# B_PCB.net
KiCad netlist of a schematic drawn in EAGLE
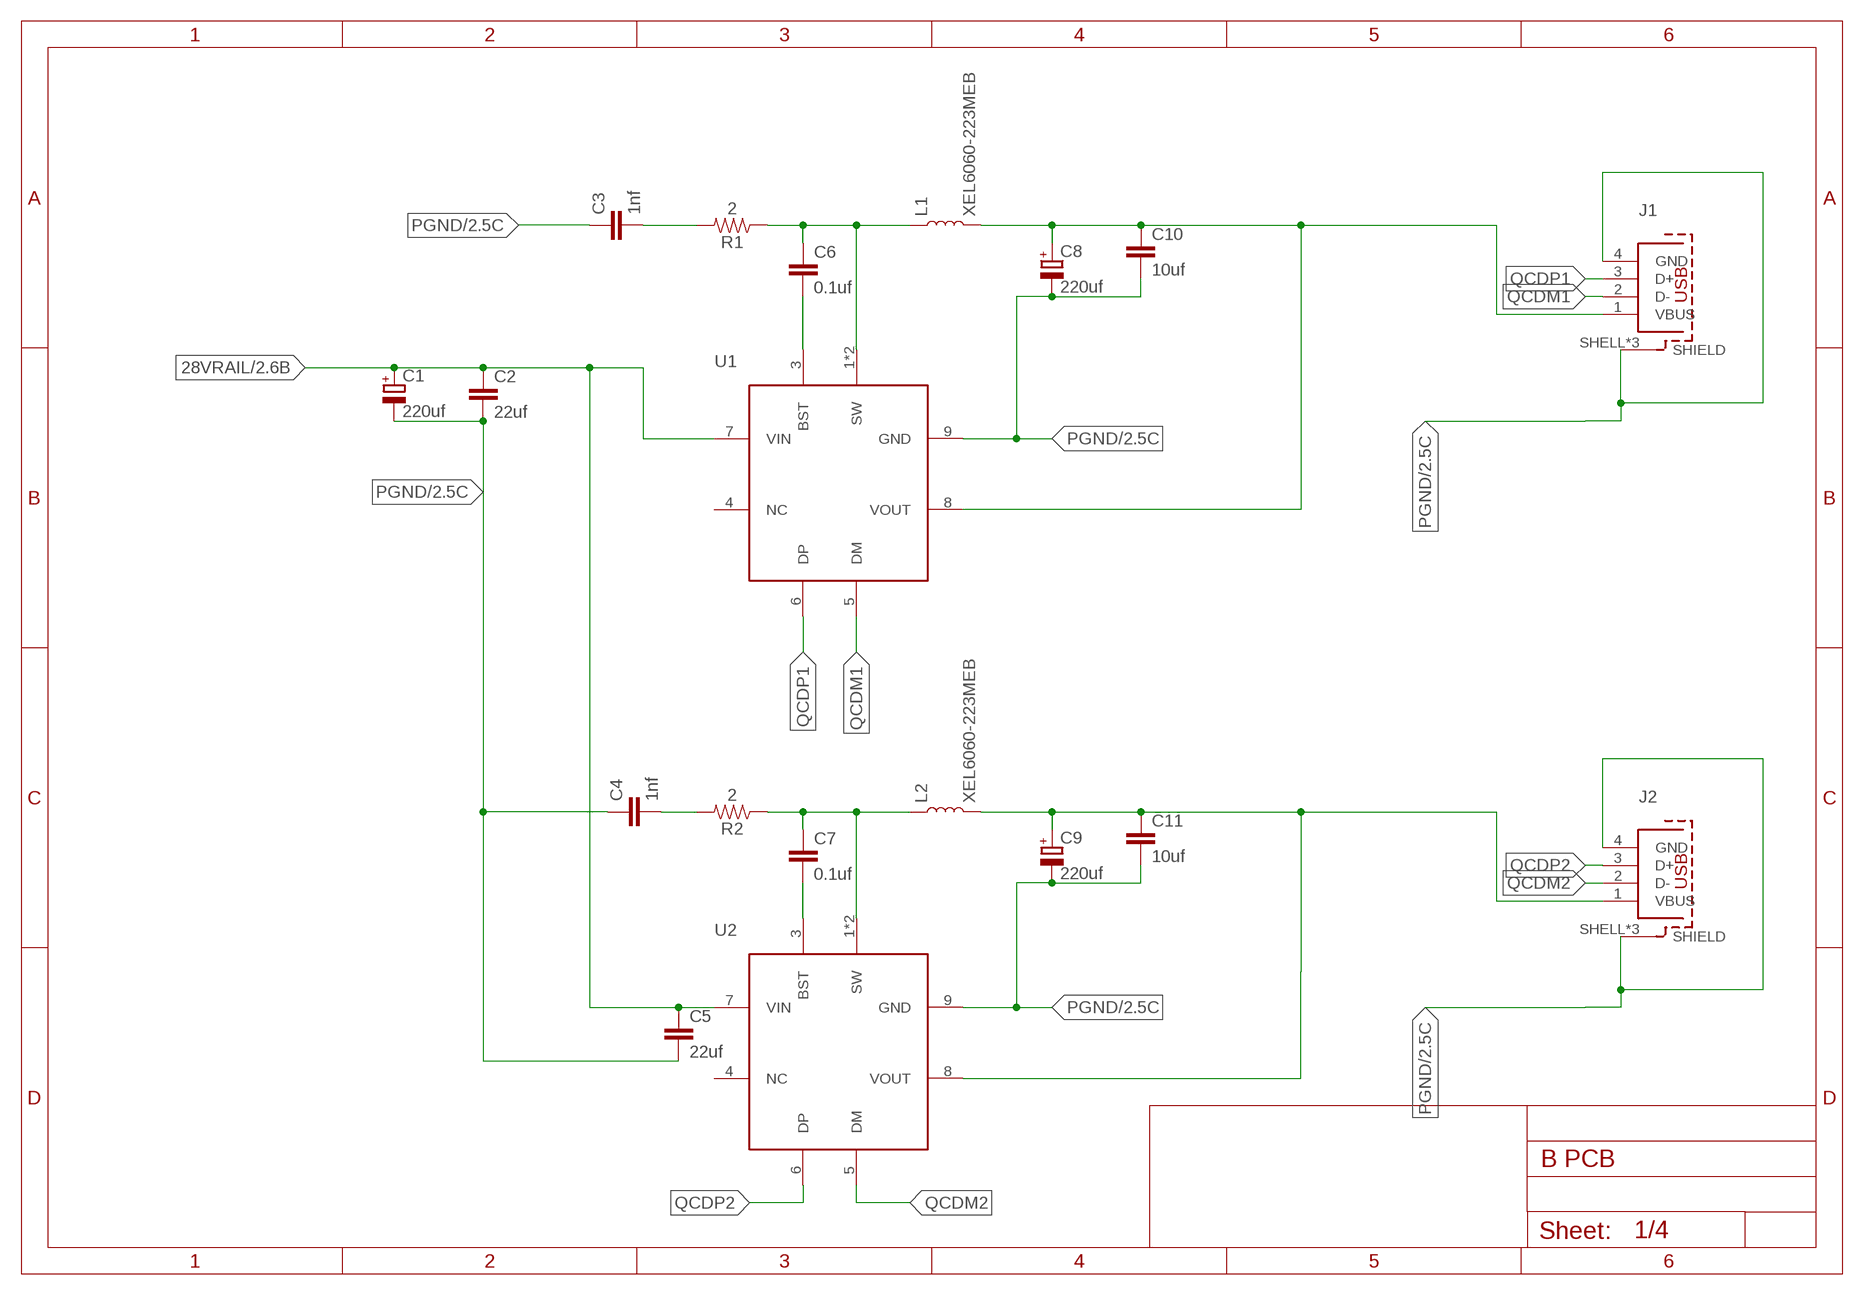
[diagram p0: schematic, sheet 1]
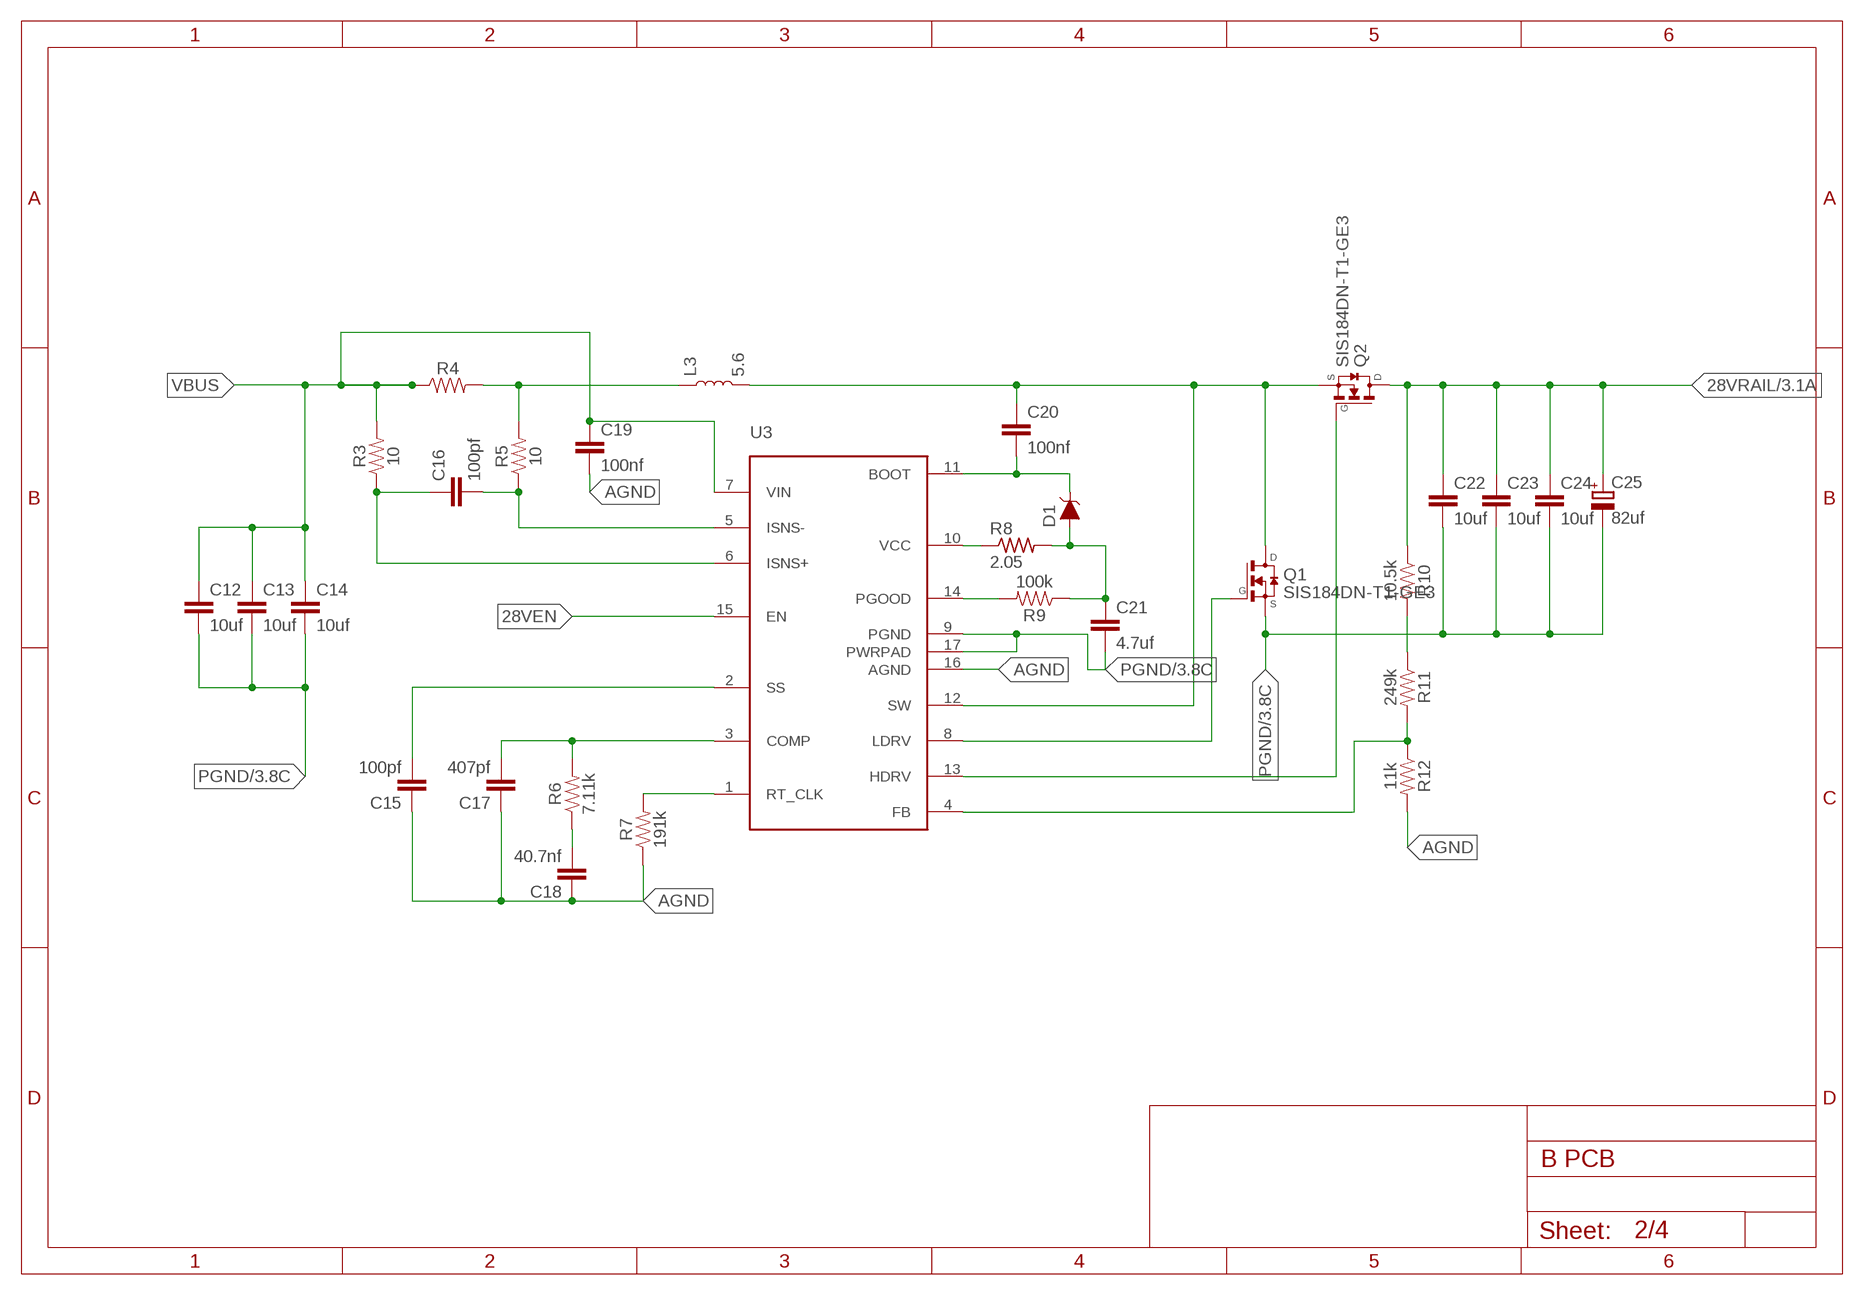
[diagram p1: schematic, sheet 2]
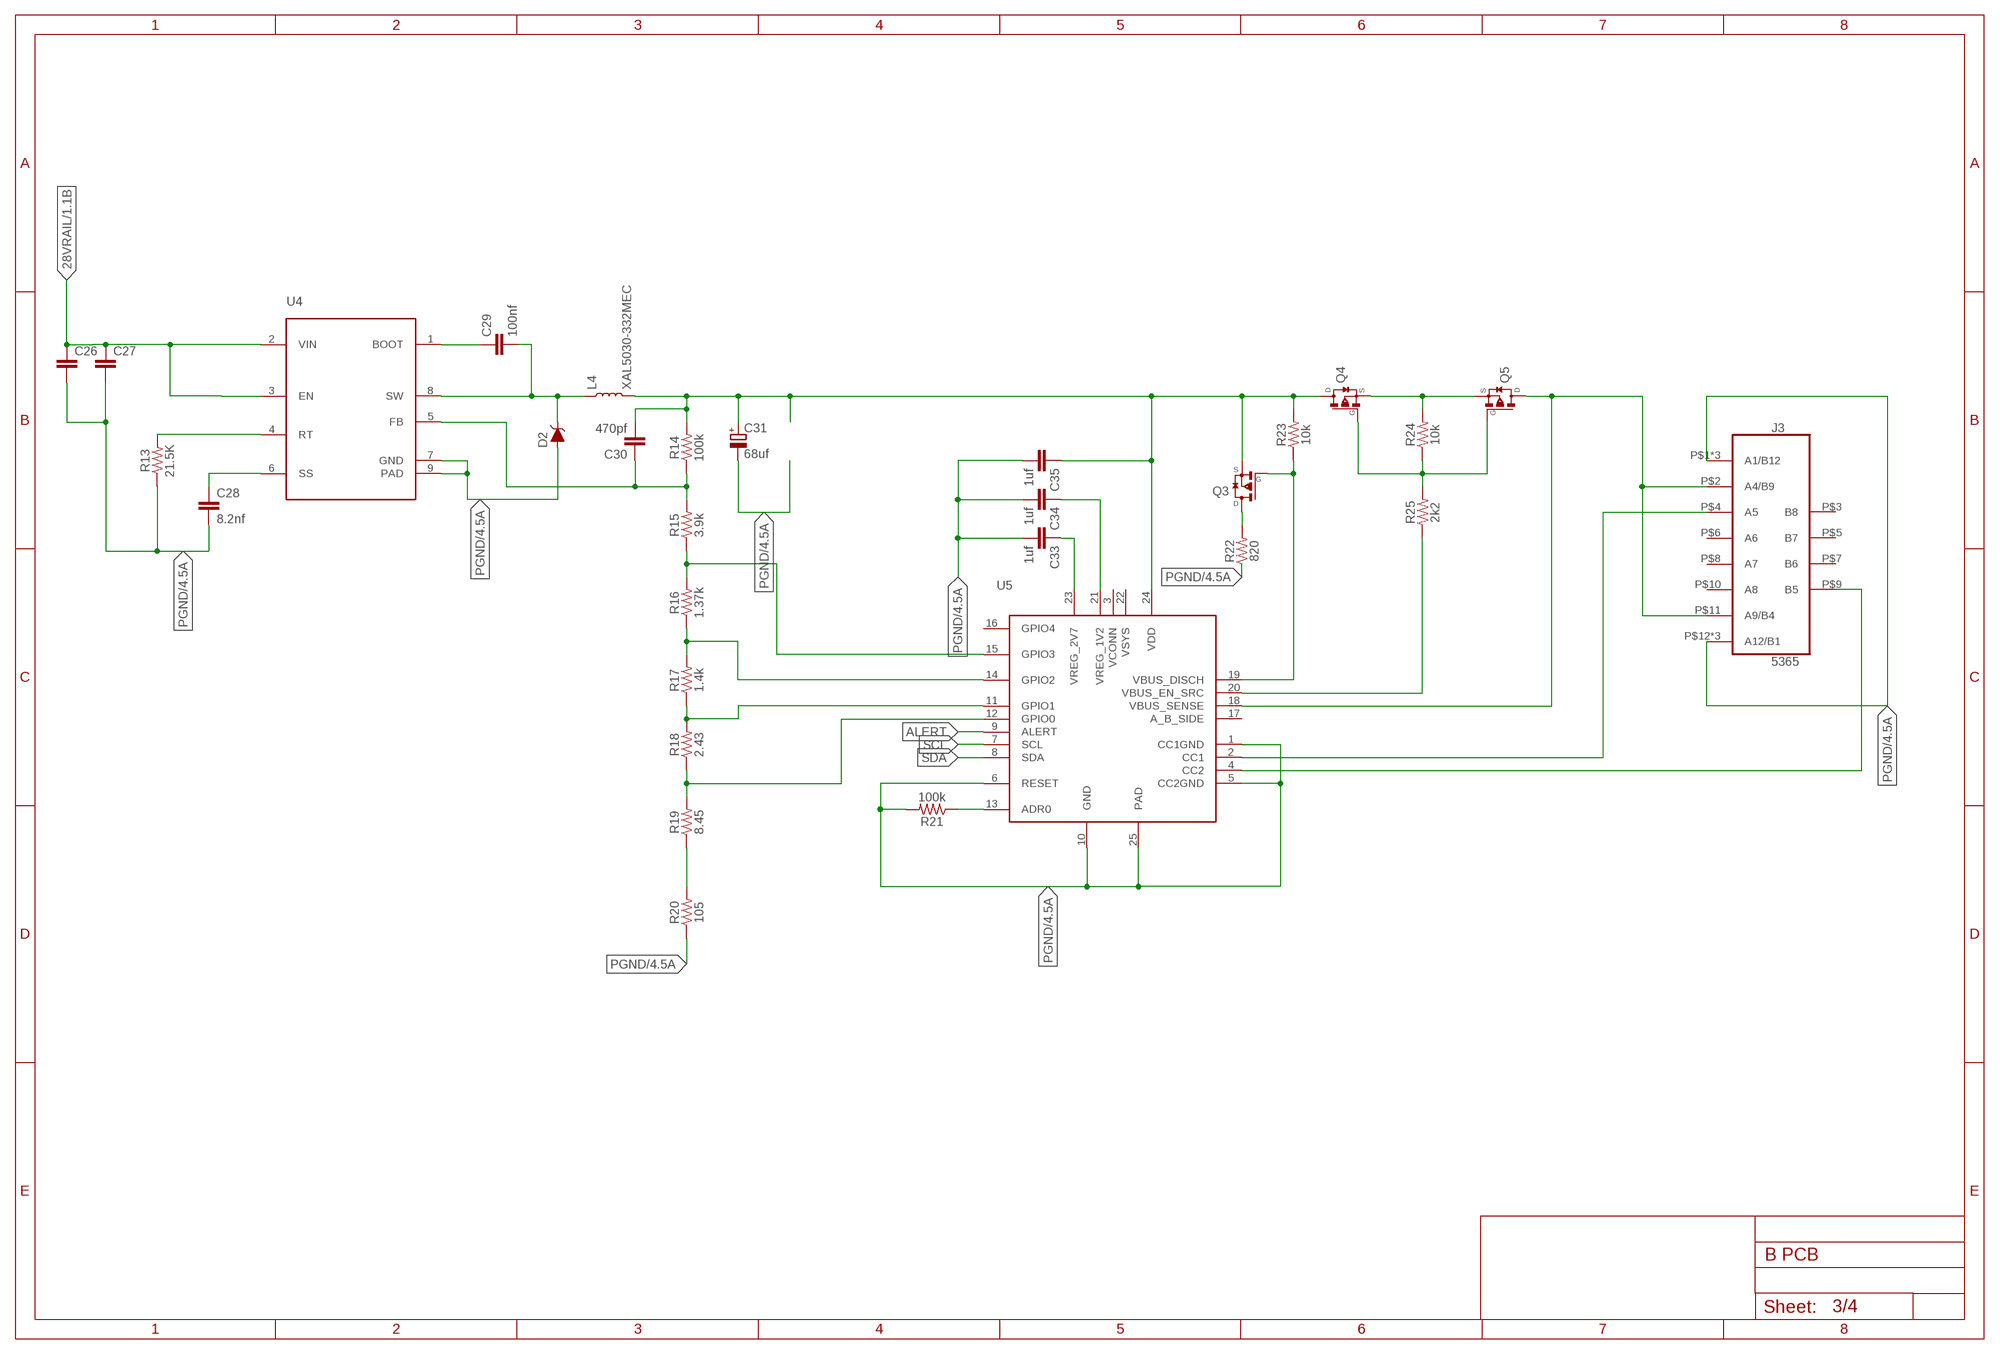
[diagram p2: schematic, sheet 3]
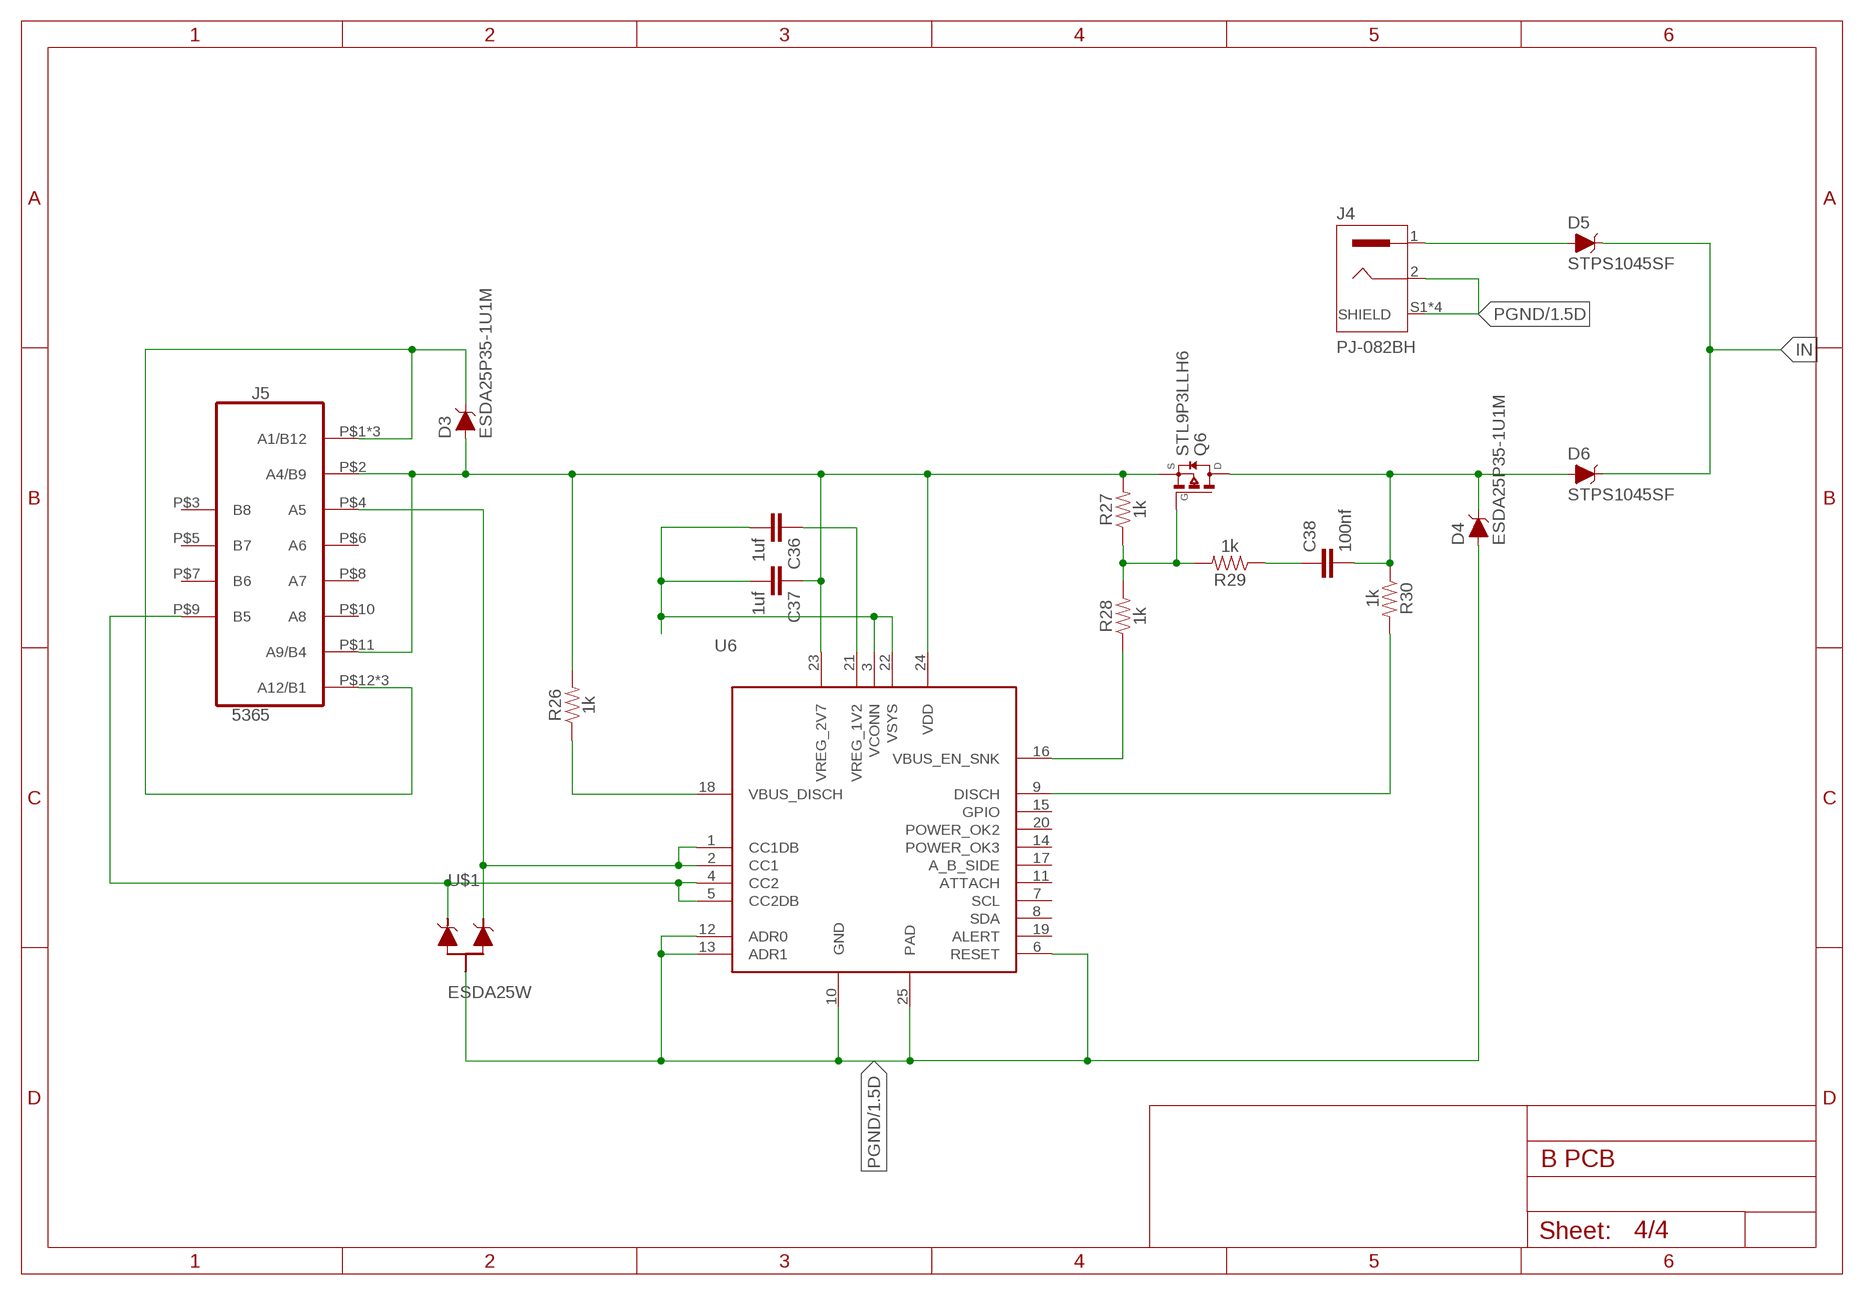
[diagram p3: schematic, sheet 4]

(export (version "E")
  (design (tool "Eeschema 10.0.6"))
  (components
    (comp (ref "C36")
      (value "1uf")
      (footprint "eagle-import:C0402K")
      (libsource (lib "eagle-import") (part "C-EUC0402K"))
    )
    (comp (ref "C37")
      (value "1uf")
      (footprint "eagle-import:C0402K")
      (libsource (lib "eagle-import") (part "C-EUC0402K"))
    )
    (comp (ref "C38")
      (value "100nf")
      (footprint "eagle-import:C0402K")
      (libsource (lib "eagle-import") (part "C-EUC0402K"))
    )
    (comp (ref "D3")
      (value "ESDA25P35-1U1M")
      (footprint "eagle-import:DIODFN160X100X60-2")
      (libsource (lib "eagle-import") (part "ESDA25P35-1U1M"))
    )
    (comp (ref "D4")
      (value "ESDA25P35-1U1M")
      (footprint "eagle-import:DIODFN160X100X60-2")
      (libsource (lib "eagle-import") (part "ESDA25P35-1U1M"))
    )
    (comp (ref "D5")
      (value "STPS1045SF")
      (footprint "eagle-import:DIODFN650X460X120-3")
      (libsource (lib "eagle-import") (part "STPS1045SF"))
    )
    (comp (ref "D6")
      (value "STPS1045SF")
      (footprint "eagle-import:DIODFN650X460X120-3")
      (libsource (lib "eagle-import") (part "STPS1045SF"))
    )
    (comp (ref "J4")
      (value "PJ-082BH")
      (footprint "eagle-import:CUI_PJ-082BH")
      (fields (field (name "MANUFACTURER") "CUI Inc."))
      (libsource (lib "eagle-import") (part "PJ-082BH"))
    )
    (comp (ref "J5")
      (value "5365")
      (footprint "eagle-import:5365")
      (libsource (lib "eagle-import") (part "5365"))
    )
    (comp (ref "Q6")
      (value "STL9P3LLH6")
      (footprint "eagle-import:SON65P330X330X80-8")
      (libsource (lib "eagle-import") (part "STL9P3LLH6"))
    )
    (comp (ref "R26")
      (value "1k")
      (footprint "eagle-import:0402")
      (libsource (lib "eagle-import") (part "RES4K04020402"))
    )
    (comp (ref "R27")
      (value "1k")
      (footprint "eagle-import:0402")
      (libsource (lib "eagle-import") (part "RES4K04020402"))
    )
    (comp (ref "R28")
      (value "1k")
      (footprint "eagle-import:0402")
      (libsource (lib "eagle-import") (part "RES4K04020402"))
    )
    (comp (ref "R29")
      (value "1k")
      (footprint "eagle-import:0402")
      (libsource (lib "eagle-import") (part "RES4K04020402"))
    )
    (comp (ref "R30")
      (value "1k")
      (footprint "eagle-import:0402")
      (libsource (lib "eagle-import") (part "RES4K04020402"))
    )
    (comp (ref "U$1")
      (value "ESDA25W")
      (footprint "eagle-import:SOT65P210X110-3")
      (libsource (lib "eagle-import") (part "ESDA25W"))
    )
    (comp (ref "U6")
      (value "STUSB4500")
      (footprint "eagle-import:QFN50P400X400X100-25T270")
      (libsource (lib "eagle-import") (part "STUSB4500"))
    )
    (comp (ref "C12")
      (value "10uf")
      (footprint "eagle-import:C0805K")
      (libsource (lib "eagle-import") (part "C-EUC0805K"))
    )
    (comp (ref "C13")
      (value "10uf")
      (footprint "eagle-import:C0805K")
      (libsource (lib "eagle-import") (part "C-EUC0805K"))
    )
    (comp (ref "C14")
      (value "10uf")
      (footprint "eagle-import:C0805K")
      (libsource (lib "eagle-import") (part "C-EUC0805K"))
    )
    (comp (ref "C15")
      (value "100pf")
      (footprint "eagle-import:C0402K")
      (libsource (lib "eagle-import") (part "C-EUC0402K"))
    )
    (comp (ref "C16")
      (value "100pf")
      (footprint "eagle-import:C0402K")
      (libsource (lib "eagle-import") (part "C-EUC0402K"))
    )
    (comp (ref "C17")
      (value "407pf")
      (footprint "eagle-import:C0402K")
      (libsource (lib "eagle-import") (part "C-EUC0402K"))
    )
    (comp (ref "C18")
      (value "40.7nf")
      (footprint "eagle-import:C0402K")
      (libsource (lib "eagle-import") (part "C-EUC0402K"))
    )
    (comp (ref "C19")
      (value "100nf")
      (footprint "eagle-import:C0402K")
      (libsource (lib "eagle-import") (part "C-EUC0402K"))
    )
    (comp (ref "C20")
      (value "100nf")
      (footprint "eagle-import:C0402K")
      (libsource (lib "eagle-import") (part "C-EUC0402K"))
    )
    (comp (ref "C21")
      (value "4.7uf")
      (footprint "eagle-import:C0402K")
      (libsource (lib "eagle-import") (part "C-EUC0402K"))
    )
    (comp (ref "C22")
      (value "10uf")
      (footprint "eagle-import:C0805K")
      (libsource (lib "eagle-import") (part "C-EUC0805K"))
    )
    (comp (ref "C23")
      (value "10uf")
      (footprint "eagle-import:C0805K")
      (libsource (lib "eagle-import") (part "C-EUC0805K"))
    )
    (comp (ref "C24")
      (value "10uf")
      (footprint "eagle-import:C0805K")
      (libsource (lib "eagle-import") (part "C-EUC0805K"))
    )
    (comp (ref "C25")
      (value "82uf")
      (footprint "eagle-import:CAPAE660X800")
      (libsource (lib "eagle-import") (part "EMZR250ARA221MF80G"))
    )
    (comp (ref "D1")
      (value "SS24FL")
      (footprint "eagle-import:SODFL3617X108")
      (libsource (lib "eagle-import") (part "SS24FL"))
    )
    (comp (ref "L3")
      (value "5.6")
      (footprint "eagle-import:RESM7275X700")
      (libsource (lib "eagle-import") (part "XAL7070-472MEB"))
    )
    (comp (ref "Q1")
      (value "SIS184DN-T1-GE3")
      (footprint "eagle-import:SIS184DN-T1-GE3")
      (libsource (lib "eagle-import") (part "SIS184DN-T1-GE3"))
    )
    (comp (ref "Q2")
      (value "SIS184DN-T1-GE3")
      (footprint "eagle-import:SIS184DN-T1-GE3")
      (libsource (lib "eagle-import") (part "SIS184DN-T1-GE3"))
    )
    (comp (ref "R3")
      (value "10")
      (footprint "eagle-import:0402")
      (libsource (lib "eagle-import") (part "RES4K04020402"))
    )
    (comp (ref "R4")
      (value "LRMAM2512-R0035FT4")
      (footprint "eagle-import:RESC6432X90")
      (libsource (lib "eagle-import") (part "LRMAM2512-R0035FT4"))
    )
    (comp (ref "R5")
      (value "10")
      (footprint "eagle-import:0402")
      (libsource (lib "eagle-import") (part "RES4K04020402"))
    )
    (comp (ref "R6")
      (value "7.11k")
      (footprint "eagle-import:0402")
      (libsource (lib "eagle-import") (part "RES4K04020402"))
    )
    (comp (ref "R7")
      (value "191k")
      (footprint "eagle-import:0402")
      (libsource (lib "eagle-import") (part "RES4K04020402"))
    )
    (comp (ref "R8")
      (value "2.05")
      (footprint "eagle-import:R0603")
      (libsource (lib "eagle-import") (part "R-US_R0603"))
    )
    (comp (ref "R9")
      (value "100k")
      (footprint "eagle-import:0402")
      (libsource (lib "eagle-import") (part "RES4K04020402"))
    )
    (comp (ref "R10")
      (value "10.5k")
      (footprint "eagle-import:0402")
      (libsource (lib "eagle-import") (part "RES4K04020402"))
    )
    (comp (ref "R11")
      (value "249k")
      (footprint "eagle-import:0402")
      (libsource (lib "eagle-import") (part "RES4K04020402"))
    )
    (comp (ref "R12")
      (value "11k")
      (footprint "eagle-import:0402")
      (libsource (lib "eagle-import") (part "RES4K04020402"))
    )
    (comp (ref "U3")
      (value "TPS43061")
      (footprint "eagle-import:QFN50P300X300X100-17T80X120")
      (libsource (lib "eagle-import") (part "TPS43061"))
    )
    (comp (ref "C1")
      (value "220uf")
      (footprint "eagle-import:CAPAE830X1040")
      (libsource (lib "eagle-import") (part "PCR1H820MCL6GS"))
    )
    (comp (ref "C2")
      (value "22uf")
      (footprint "eagle-import:C0805K")
      (libsource (lib "eagle-import") (part "C-EUC0805K"))
    )
    (comp (ref "C3")
      (value "1nf")
      (footprint "eagle-import:C0402K")
      (libsource (lib "eagle-import") (part "C-EUC0402K"))
    )
    (comp (ref "C4")
      (value "1nf")
      (footprint "eagle-import:C0402K")
      (libsource (lib "eagle-import") (part "C-EUC0402K"))
    )
    (comp (ref "C5")
      (value "22uf")
      (footprint "eagle-import:C0805K")
      (libsource (lib "eagle-import") (part "C-EUC0805K"))
    )
    (comp (ref "C6")
      (value "0.1uf")
      (footprint "eagle-import:C0805K")
      (libsource (lib "eagle-import") (part "C-EUC0805K"))
    )
    (comp (ref "C7")
      (value "0.1uf")
      (footprint "eagle-import:C0805K")
      (libsource (lib "eagle-import") (part "C-EUC0805K"))
    )
    (comp (ref "C8")
      (value "220uf")
      (footprint "eagle-import:CAPAE660X800")
      (libsource (lib "eagle-import") (part "EMZR250ARA221MF80G"))
    )
    (comp (ref "C9")
      (value "220uf")
      (footprint "eagle-import:CAPAE660X800")
      (libsource (lib "eagle-import") (part "EMZR250ARA221MF80G"))
    )
    (comp (ref "C10")
      (value "10uf")
      (footprint "eagle-import:C0805K")
      (libsource (lib "eagle-import") (part "C-EUC0805K"))
    )
    (comp (ref "C11")
      (value "10uf")
      (footprint "eagle-import:C0805K")
      (libsource (lib "eagle-import") (part "C-EUC0805K"))
    )
    (comp (ref "J1")
      (value "614004184726")
      (footprint "eagle-import:614004184726")
      (libsource (lib "eagle-import") (part "614004184726"))
    )
    (comp (ref "J2")
      (value "614004184726")
      (footprint "eagle-import:614004184726")
      (libsource (lib "eagle-import") (part "614004184726"))
    )
    (comp (ref "L1")
      (value "XEL6060-223MEB")
      (footprint "eagle-import:RESM6365X610")
      (libsource (lib "eagle-import") (part "XEL6060-222MEB"))
    )
    (comp (ref "L2")
      (value "XEL6060-223MEB")
      (footprint "eagle-import:RESM6365X610")
      (libsource (lib "eagle-import") (part "XEL6060-222MEB"))
    )
    (comp (ref "R1")
      (value "2")
      (footprint "eagle-import:0402")
      (libsource (lib "eagle-import") (part "RES4K04020402"))
    )
    (comp (ref "R2")
      (value "2")
      (footprint "eagle-import:0402")
      (libsource (lib "eagle-import") (part "RES4K04020402"))
    )
    (comp (ref "U1")
      (value "IP6505")
      (footprint "eagle-import:SOIC127P600X165-9T209")
      (libsource (lib "eagle-import") (part "IP6505"))
    )
    (comp (ref "U2")
      (value "IP6505")
      (footprint "eagle-import:SOIC127P600X165-9T209")
      (libsource (lib "eagle-import") (part "IP6505"))
    )
    (comp (ref "C26")
      (value "C-EUC1210")
      (footprint "eagle-import:C1210")
      (libsource (lib "eagle-import") (part "C-EUC1210"))
    )
    (comp (ref "C27")
      (value "C-EUC1210")
      (footprint "eagle-import:C1210")
      (libsource (lib "eagle-import") (part "C-EUC1210"))
    )
    (comp (ref "C28")
      (value "8.2nf")
      (footprint "eagle-import:C0402K")
      (libsource (lib "eagle-import") (part "C-EUC0402K"))
    )
    (comp (ref "C29")
      (value "100nf")
      (footprint "eagle-import:C0402K")
      (libsource (lib "eagle-import") (part "C-EUC0402K"))
    )
    (comp (ref "C30")
      (value "470pf")
      (footprint "eagle-import:C0402K")
      (libsource (lib "eagle-import") (part "C-EUC0402K"))
    )
    (comp (ref "C31")
      (value "68uf")
      (footprint "eagle-import:CAPAE830X1040")
      (libsource (lib "eagle-import") (part "PCR1H820MCL6GS"))
    )
    (comp (ref "C33")
      (value "1uf")
      (footprint "eagle-import:C0402K")
      (libsource (lib "eagle-import") (part "C-EUC0402K"))
    )
    (comp (ref "C34")
      (value "1uf")
      (footprint "eagle-import:C0402K")
      (libsource (lib "eagle-import") (part "C-EUC0402K"))
    )
    (comp (ref "C35")
      (value "1uf")
      (footprint "eagle-import:C0402K")
      (libsource (lib "eagle-import") (part "C-EUC0402K"))
    )
    (comp (ref "D2")
      (value "B560C-13-F")
      (footprint "eagle-import:DIOM6859X250")
      (libsource (lib "eagle-import") (part "B560C-13-F"))
    )
    (comp (ref "J3")
      (value "5365")
      (footprint "eagle-import:5365")
      (libsource (lib "eagle-import") (part "5365"))
    )
    (comp (ref "L4")
      (value "XAL5030-332MEC")
      (footprint "eagle-import:INDM5355X310")
      (libsource (lib "eagle-import") (part "XAL5030-332MEC"))
    )
    (comp (ref "Q3")
      (value "STR2P3LLH6")
      (footprint "eagle-import:SOT95P280X125-3")
      (libsource (lib "eagle-import") (part "STR2P3LLH6"))
    )
    (comp (ref "Q4")
      (value "STL9P3LLH6")
      (footprint "eagle-import:SON65P330X330X80-8")
      (libsource (lib "eagle-import") (part "STL9P3LLH6"))
    )
    (comp (ref "Q5")
      (value "STL9P3LLH6")
      (footprint "eagle-import:SON65P330X330X80-8")
      (libsource (lib "eagle-import") (part "STL9P3LLH6"))
    )
    (comp (ref "R13")
      (value "21.5K")
      (footprint "eagle-import:0402")
      (libsource (lib "eagle-import") (part "RES4K04020402"))
    )
    (comp (ref "R14")
      (value "100k")
      (footprint "eagle-import:0402")
      (libsource (lib "eagle-import") (part "RES4K04020402"))
    )
    (comp (ref "R15")
      (value "3.9k")
      (footprint "eagle-import:0402")
      (libsource (lib "eagle-import") (part "RES4K04020402"))
    )
    (comp (ref "R16")
      (value "1.37k")
      (footprint "eagle-import:0402")
      (libsource (lib "eagle-import") (part "RES4K04020402"))
    )
    (comp (ref "R17")
      (value "1.4k")
      (footprint "eagle-import:0402")
      (libsource (lib "eagle-import") (part "RES4K04020402"))
    )
    (comp (ref "R18")
      (value "2.43")
      (footprint "eagle-import:0402")
      (libsource (lib "eagle-import") (part "RES4K04020402"))
    )
    (comp (ref "R19")
      (value "8.45")
      (footprint "eagle-import:0402")
      (libsource (lib "eagle-import") (part "RES4K04020402"))
    )
    (comp (ref "R20")
      (value "105")
      (footprint "eagle-import:0402")
      (libsource (lib "eagle-import") (part "RES4K04020402"))
    )
    (comp (ref "R21")
      (value "100k")
      (footprint "eagle-import:0402")
      (fields (field (name "SPICEPREFIX") "R"))
      (libsource (lib "eagle-import") (part "RES4K04020402"))
    )
    (comp (ref "R22")
      (value "820")
      (footprint "eagle-import:0402")
      (libsource (lib "eagle-import") (part "RES4K04020402"))
    )
    (comp (ref "R23")
      (value "10k")
      (footprint "eagle-import:0402")
      (libsource (lib "eagle-import") (part "RES4K04020402"))
    )
    (comp (ref "R24")
      (value "10k")
      (footprint "eagle-import:0402")
      (libsource (lib "eagle-import") (part "RES4K04020402"))
    )
    (comp (ref "R25")
      (value "2k2")
      (footprint "eagle-import:0402")
      (libsource (lib "eagle-import") (part "RES4K04020402"))
    )
    (comp (ref "U4")
      (value "LMR14050")
      (footprint "eagle-import:SOIC127P600X170-9T240X260")
      (libsource (lib "eagle-import") (part "LMR14050"))
    )
    (comp (ref "U5")
      (value "STUSB4700")
      (footprint "eagle-import:QFN50P400X400X100-25T270")
      (libsource (lib "eagle-import") (part "STUSB4700"))
    )
  )
  (nets
    (net (code "1") (name "28VEN") (class "Default")
      (node (ref "U3") (pin "15") (pinfunction "EN_15") (pintype "bidirectional"))
    )
    (net (code "2") (name "28VRAIL") (class "Default")
      (node (ref "C1") (pin "1") (pinfunction "+_1") (pintype "passive"))
      (node (ref "C2") (pin "1") (pinfunction "1_1") (pintype "passive"))
      (node (ref "C22") (pin "1") (pinfunction "1_1") (pintype "passive"))
      (node (ref "C23") (pin "1") (pinfunction "1_1") (pintype "passive"))
      (node (ref "C24") (pin "1") (pinfunction "1_1") (pintype "passive"))
      (node (ref "C25") (pin "1") (pinfunction "+_1") (pintype "passive"))
      (node (ref "C26") (pin "1") (pinfunction "1_1") (pintype "passive"))
      (node (ref "C27") (pin "1") (pinfunction "1_1") (pintype "passive"))
      (node (ref "C5") (pin "1") (pinfunction "1_1") (pintype "passive"))
      (node (ref "Q2") (pin "P$5") (pinfunction "D_P$5") (pintype "passive"))
      (node (ref "Q2") (pin "P$6") (pinfunction "D_P$6") (pintype "passive"))
      (node (ref "Q2") (pin "P$7") (pinfunction "D_P$7") (pintype "passive"))
      (node (ref "Q2") (pin "P$8") (pinfunction "D_P$8") (pintype "passive"))
      (node (ref "Q2") (pin "P$9") (pinfunction "D_P$9") (pintype "passive"))
      (node (ref "R10") (pin "1") (pinfunction "1_1") (pintype "passive"))
      (node (ref "U1") (pin "7") (pinfunction "VIN_7") (pintype "bidirectional"))
      (node (ref "U2") (pin "7") (pinfunction "VIN_7") (pintype "bidirectional"))
      (node (ref "U4") (pin "2") (pinfunction "VIN_2") (pintype "bidirectional"))
      (node (ref "U4") (pin "3") (pinfunction "EN_3") (pintype "bidirectional"))
    )
    (net (code "3") (name "AGND") (class "Default")
      (node (ref "C15") (pin "1") (pinfunction "1_1") (pintype "passive"))
      (node (ref "C17") (pin "1") (pinfunction "1_1") (pintype "passive"))
      (node (ref "C18") (pin "1") (pinfunction "1_1") (pintype "passive"))
      (node (ref "C19") (pin "2") (pinfunction "2_2") (pintype "passive"))
      (node (ref "R12") (pin "2") (pinfunction "2_2") (pintype "passive"))
      (node (ref "R7") (pin "1") (pinfunction "1_1") (pintype "passive"))
      (node (ref "U3") (pin "16") (pinfunction "AGND_16") (pintype "bidirectional"))
    )
    (net (code "4") (name "ALERT") (class "Default")
      (node (ref "U5") (pin "9") (pinfunction "ALERT_9") (pintype "bidirectional"))
    )
    (net (code "5") (name "IN") (class "Default")
      (node (ref "D5") (pin "3") (pinfunction "C_3") (pintype "passive"))
      (node (ref "D6") (pin "3") (pinfunction "C_3") (pintype "passive"))
    )
    (net (code "6") (name "Net-(C3-Pad2)") (class "Default")
      (node (ref "C3") (pin "2") (pinfunction "2_2") (pintype "passive"))
      (node (ref "R1") (pin "2") (pinfunction "2_2") (pintype "passive"))
    )
    (net (code "7") (name "Net-(C4-Pad2)") (class "Default")
      (node (ref "C4") (pin "2") (pinfunction "2_2") (pintype "passive"))
      (node (ref "R2") (pin "2") (pinfunction "2_2") (pintype "passive"))
    )
    (net (code "8") (name "Net-(C6-Pad1)") (class "Default")
      (node (ref "C6") (pin "1") (pinfunction "1_1") (pintype "passive"))
      (node (ref "L1") (pin "1") (pinfunction "1_1") (pintype "passive"))
      (node (ref "R1") (pin "1") (pinfunction "1_1") (pintype "passive"))
      (node (ref "U1") (pin "1") (pinfunction "SW_1") (pintype "bidirectional"))
      (node (ref "U1") (pin "2") (pinfunction "SW_2") (pintype "bidirectional"))
    )
    (net (code "9") (name "Net-(C7-Pad1)") (class "Default")
      (node (ref "C7") (pin "1") (pinfunction "1_1") (pintype "passive"))
      (node (ref "L2") (pin "1") (pinfunction "1_1") (pintype "passive"))
      (node (ref "R2") (pin "1") (pinfunction "1_1") (pintype "passive"))
      (node (ref "U2") (pin "1") (pinfunction "SW_1") (pintype "bidirectional"))
      (node (ref "U2") (pin "2") (pinfunction "SW_2") (pintype "bidirectional"))
    )
    (net (code "10") (name "Net-(C8-+)") (class "Default")
      (node (ref "C10") (pin "1") (pinfunction "1_1") (pintype "passive"))
      (node (ref "C8") (pin "1") (pinfunction "+_1") (pintype "passive"))
      (node (ref "J1") (pin "1") (pinfunction "VBUS_1") (pintype "bidirectional"))
      (node (ref "L1") (pin "2") (pinfunction "2_2") (pintype "passive"))
      (node (ref "U1") (pin "8") (pinfunction "VOUT_8") (pintype "bidirectional"))
    )
    (net (code "11") (name "Net-(C9-+)") (class "Default")
      (node (ref "C11") (pin "1") (pinfunction "1_1") (pintype "passive"))
      (node (ref "C9") (pin "1") (pinfunction "+_1") (pintype "passive"))
      (node (ref "J2") (pin "1") (pinfunction "VBUS_1") (pintype "bidirectional"))
      (node (ref "L2") (pin "2") (pinfunction "2_2") (pintype "passive"))
      (node (ref "U2") (pin "8") (pinfunction "VOUT_8") (pintype "bidirectional"))
    )
    (net (code "12") (name "Net-(C18-Pad2)") (class "Default")
      (node (ref "C18") (pin "2") (pinfunction "2_2") (pintype "passive"))
      (node (ref "R6") (pin "1") (pinfunction "1_1") (pintype "passive"))
    )
    (net (code "13") (name "Net-(C31-+)") (class "Default")
      (node (ref "C30") (pin "2") (pinfunction "2_2") (pintype "passive"))
      (node (ref "C31") (pin "1") (pinfunction "+_1") (pintype "passive"))
      (node (ref "C35") (pin "1") (pinfunction "1_1") (pintype "passive"))
      (node (ref "L4") (pin "2") (pinfunction "2_2") (pintype "passive"))
      (node (ref "Q3") (pin "2") (pinfunction "S_2") (pintype "passive"))
      (node (ref "Q4") (pin "5") (pinfunction "D_5") (pintype "passive"))
      (node (ref "Q4") (pin "6") (pinfunction "D_6") (pintype "passive"))
      (node (ref "Q4") (pin "7") (pinfunction "D_7") (pintype "passive"))
      (node (ref "R14") (pin "2") (pinfunction "2_2") (pintype "passive"))
      (node (ref "R23") (pin "2") (pinfunction "2_2") (pintype "passive"))
      (node (ref "U5") (pin "24") (pinfunction "VDD_24") (pintype "bidirectional"))
    )
    (net (code "14") (name "Net-(C38-Pad1)") (class "Default")
      (node (ref "C38") (pin "1") (pinfunction "1_1") (pintype "passive"))
      (node (ref "R29") (pin "1") (pinfunction "1_1") (pintype "passive"))
    )
    (net (code "15") (name "Net-(D1-A)") (class "Default")
      (node (ref "C21") (pin "1") (pinfunction "1_1") (pintype "passive"))
      (node (ref "D1") (pin "2") (pinfunction "A_2") (pintype "passive"))
      (node (ref "R8") (pin "2") (pinfunction "2_2") (pintype "passive"))
      (node (ref "R9") (pin "1") (pinfunction "1_1") (pintype "passive"))
    )
    (net (code "16") (name "Net-(D1-C)") (class "Default")
      (node (ref "C20") (pin "2") (pinfunction "2_2") (pintype "passive"))
      (node (ref "D1") (pin "1") (pinfunction "C_1") (pintype "passive"))
      (node (ref "U3") (pin "11") (pinfunction "BOOT_11") (pintype "bidirectional"))
    )
    (net (code "17") (name "Net-(D2-C)") (class "Default")
      (node (ref "C29") (pin "2") (pinfunction "2_2") (pintype "passive"))
      (node (ref "D2") (pin "1") (pinfunction "C_1") (pintype "passive"))
      (node (ref "L4") (pin "1") (pinfunction "1_1") (pintype "passive"))
      (node (ref "U4") (pin "8") (pinfunction "SW_8") (pintype "bidirectional"))
    )
    (net (code "18") (name "Net-(D3-A)") (class "Default")
      (node (ref "C37") (pin "1") (pinfunction "1_1") (pintype "passive"))
      (node (ref "D3") (pin "2") (pinfunction "A_2") (pintype "passive"))
      (node (ref "J5") (pin "P$11") (pinfunction "A9/B4_P$11") (pintype "bidirectional"))
      (node (ref "J5") (pin "P$2") (pinfunction "A4/B9_P$2") (pintype "bidirectional"))
      (node (ref "Q6") (pin "1") (pinfunction "S_1") (pintype "passive"))
      (node (ref "Q6") (pin "2") (pinfunction "S_2") (pintype "passive"))
      (node (ref "Q6") (pin "3") (pinfunction "S_3") (pintype "passive"))
      (node (ref "R26") (pin "2") (pinfunction "2_2") (pintype "passive"))
      (node (ref "R27") (pin "2") (pinfunction "2_2") (pintype "passive"))
      (node (ref "U6") (pin "23") (pinfunction "VREG_2V7_23") (pintype "bidirectional"))
      (node (ref "U6") (pin "24") (pinfunction "VDD_24") (pintype "bidirectional"))
    )
    (net (code "19") (name "Net-(D3-C)") (class "Default")
      (node (ref "D3") (pin "1") (pinfunction "C_1") (pintype "passive"))
      (node (ref "J5") (pin "P$1") (pinfunction "A1/B12_P$1") (pintype "bidirectional"))
      (node (ref "J5") (pin "P$12") (pinfunction "A12/B1_P$12") (pintype "bidirectional"))
      (node (ref "J5") (pin "P$13") (pinfunction "A1/B12_P$13") (pintype "bidirectional"))
      (node (ref "J5") (pin "P$14") (pinfunction "A12/B1_P$14") (pintype "bidirectional"))
      (node (ref "J5") (pin "P$15") (pinfunction "A1/B12_P$15") (pintype "bidirectional"))
      (node (ref "J5") (pin "P$16") (pinfunction "A12/B1_P$16") (pintype "bidirectional"))
    )
    (net (code "20") (name "Net-(D4-C)") (class "Default")
      (node (ref "C38") (pin "2") (pinfunction "2_2") (pintype "passive"))
      (node (ref "D4") (pin "1") (pinfunction "C_1") (pintype "passive"))
      (node (ref "D6") (pin "1") (pinfunction "A_1") (pintype "passive"))
      (node (ref "D6") (pin "2") (pinfunction "A_2") (pintype "passive"))
      (node (ref "Q6") (pin "5") (pinfunction "D_5") (pintype "passive"))
      (node (ref "Q6") (pin "6") (pinfunction "D_6") (pintype "passive"))
      (node (ref "Q6") (pin "7") (pinfunction "D_7") (pintype "passive"))
      (node (ref "R30") (pin "1") (pinfunction "1_1") (pintype "passive"))
    )
    (net (code "21") (name "Net-(D5-A-Pad1)") (class "Default")
      (node (ref "D5") (pin "1") (pinfunction "A_1") (pintype "passive"))
      (node (ref "D5") (pin "2") (pinfunction "A_2") (pintype "passive"))
      (node (ref "J4") (pin "1") (pinfunction "1_1") (pintype "passive"))
    )
    (net (code "22") (name "Net-(J3-A4{slash}B9)") (class "Default")
      (node (ref "J3") (pin "P$11") (pinfunction "A9/B4_P$11") (pintype "bidirectional"))
      (node (ref "J3") (pin "P$2") (pinfunction "A4/B9_P$2") (pintype "bidirectional"))
      (node (ref "Q5") (pin "5") (pinfunction "D_5") (pintype "passive"))
      (node (ref "Q5") (pin "6") (pinfunction "D_6") (pintype "passive"))
      (node (ref "Q5") (pin "7") (pinfunction "D_7") (pintype "passive"))
      (node (ref "U5") (pin "18") (pinfunction "VBUS_SENSE_18") (pintype "bidirectional"))
    )
    (net (code "23") (name "Net-(J3-A5)") (class "Default")
      (node (ref "J3") (pin "P$4") (pinfunction "A5_P$4") (pintype "bidirectional"))
      (node (ref "U5") (pin "2") (pinfunction "CC1_2") (pintype "bidirectional"))
    )
    (net (code "24") (name "Net-(J3-B5)") (class "Default")
      (node (ref "J3") (pin "P$9") (pinfunction "B5_P$9") (pintype "bidirectional"))
      (node (ref "U5") (pin "4") (pinfunction "CC2_4") (pintype "bidirectional"))
    )
    (net (code "25") (name "Net-(J5-A5)") (class "Default")
      (node (ref "J5") (pin "P$4") (pinfunction "A5_P$4") (pintype "bidirectional"))
      (node (ref "U$1") (pin "2") (pinfunction "C2_2") (pintype "passive"))
      (node (ref "U6") (pin "1") (pinfunction "CC1DB_1") (pintype "bidirectional"))
      (node (ref "U6") (pin "2") (pinfunction "CC1_2") (pintype "bidirectional"))
    )
    (net (code "26") (name "Net-(J5-B5)") (class "Default")
      (node (ref "J5") (pin "P$9") (pinfunction "B5_P$9") (pintype "bidirectional"))
      (node (ref "U$1") (pin "1") (pinfunction "C1_1") (pintype "passive"))
      (node (ref "U6") (pin "4") (pinfunction "CC2_4") (pintype "bidirectional"))
      (node (ref "U6") (pin "5") (pinfunction "CC2DB_5") (pintype "bidirectional"))
    )
    (net (code "27") (name "Net-(L3-Pad1)") (class "Default")
      (node (ref "L3") (pin "1") (pinfunction "1_1") (pintype "passive"))
      (node (ref "R4") (pin "2") (pinfunction "2_2") (pintype "passive"))
      (node (ref "R5") (pin "2") (pinfunction "2_2") (pintype "passive"))
    )
    (net (code "28") (name "Net-(Q1-G)") (class "Default")
      (node (ref "Q1") (pin "P$4") (pinfunction "G_P$4") (pintype "passive"))
      (node (ref "U3") (pin "8") (pinfunction "LDRV_8") (pintype "bidirectional"))
    )
    (net (code "29") (name "Net-(Q2-G)") (class "Default")
      (node (ref "Q2") (pin "P$4") (pinfunction "G_P$4") (pintype "passive"))
      (node (ref "U3") (pin "13") (pinfunction "HDRV_13") (pintype "bidirectional"))
    )
    (net (code "30") (name "Net-(Q3-D)") (class "Default")
      (node (ref "Q3") (pin "3") (pinfunction "D_3") (pintype "passive"))
      (node (ref "R22") (pin "2") (pinfunction "2_2") (pintype "passive"))
    )
    (net (code "31") (name "Net-(Q3-G)") (class "Default")
      (node (ref "Q3") (pin "1") (pinfunction "G_1") (pintype "passive"))
      (node (ref "R23") (pin "1") (pinfunction "1_1") (pintype "passive"))
      (node (ref "U5") (pin "19") (pinfunction "VBUS_DISCH_19") (pintype "bidirectional"))
    )
    (net (code "32") (name "Net-(Q4-G)") (class "Default")
      (node (ref "Q4") (pin "4") (pinfunction "G_4") (pintype "passive"))
      (node (ref "Q5") (pin "4") (pinfunction "G_4") (pintype "passive"))
      (node (ref "R24") (pin "1") (pinfunction "1_1") (pintype "passive"))
      (node (ref "R25") (pin "2") (pinfunction "2_2") (pintype "passive"))
    )
    (net (code "33") (name "Net-(Q4-S-Pad1)") (class "Default")
      (node (ref "Q4") (pin "1") (pinfunction "S_1") (pintype "passive"))
      (node (ref "Q4") (pin "2") (pinfunction "S_2") (pintype "passive"))
      (node (ref "Q4") (pin "3") (pinfunction "S_3") (pintype "passive"))
      (node (ref "Q5") (pin "1") (pinfunction "S_1") (pintype "passive"))
      (node (ref "Q5") (pin "2") (pinfunction "S_2") (pintype "passive"))
      (node (ref "Q5") (pin "3") (pinfunction "S_3") (pintype "passive"))
      (node (ref "R24") (pin "2") (pinfunction "2_2") (pintype "passive"))
    )
    (net (code "34") (name "Net-(Q6-G)") (class "Default")
      (node (ref "Q6") (pin "4") (pinfunction "G_4") (pintype "passive"))
      (node (ref "R27") (pin "1") (pinfunction "1_1") (pintype "passive"))
      (node (ref "R28") (pin "2") (pinfunction "2_2") (pintype "passive"))
      (node (ref "R29") (pin "2") (pinfunction "2_2") (pintype "passive"))
    )
    (net (code "35") (name "Net-(R10-Pad2)") (class "Default")
      (node (ref "R10") (pin "2") (pinfunction "2_2") (pintype "passive"))
      (node (ref "R11") (pin "1") (pinfunction "1_1") (pintype "passive"))
    )
    (net (code "36") (name "Net-(R19-Pad1)") (class "Default")
      (node (ref "R19") (pin "1") (pinfunction "1_1") (pintype "passive"))
      (node (ref "R20") (pin "2") (pinfunction "2_2") (pintype "passive"))
    )
    (net (code "37") (name "Net-(U1-BST)") (class "Default")
      (node (ref "C6") (pin "2") (pinfunction "2_2") (pintype "passive"))
      (node (ref "U1") (pin "3") (pinfunction "BST_3") (pintype "bidirectional"))
    )
    (net (code "38") (name "Net-(U2-BST)") (class "Default")
      (node (ref "C7") (pin "2") (pinfunction "2_2") (pintype "passive"))
      (node (ref "U2") (pin "3") (pinfunction "BST_3") (pintype "bidirectional"))
    )
    (net (code "39") (name "Net-(U3-COMP)") (class "Default")
      (node (ref "C17") (pin "2") (pinfunction "2_2") (pintype "passive"))
      (node (ref "R6") (pin "2") (pinfunction "2_2") (pintype "passive"))
      (node (ref "U3") (pin "3") (pinfunction "COMP_3") (pintype "bidirectional"))
    )
    (net (code "40") (name "Net-(U3-FB)") (class "Default")
      (node (ref "R11") (pin "2") (pinfunction "2_2") (pintype "passive"))
      (node (ref "R12") (pin "1") (pinfunction "1_1") (pintype "passive"))
      (node (ref "U3") (pin "4") (pinfunction "FB_4") (pintype "bidirectional"))
    )
    (net (code "41") (name "Net-(U3-ISNS+)") (class "Default")
      (node (ref "C16") (pin "1") (pinfunction "1_1") (pintype "passive"))
      (node (ref "R3") (pin "1") (pinfunction "1_1") (pintype "passive"))
      (node (ref "U3") (pin "6") (pinfunction "ISNS+_6") (pintype "bidirectional"))
    )
    (net (code "42") (name "Net-(U3-ISNS-)") (class "Default")
      (node (ref "C16") (pin "2") (pinfunction "2_2") (pintype "passive"))
      (node (ref "R5") (pin "1") (pinfunction "1_1") (pintype "passive"))
      (node (ref "U3") (pin "5") (pinfunction "ISNS-_5") (pintype "bidirectional"))
    )
    (net (code "43") (name "Net-(U3-PGOOD)") (class "Default")
      (node (ref "R9") (pin "2") (pinfunction "2_2") (pintype "passive"))
      (node (ref "U3") (pin "14") (pinfunction "PGOOD_14") (pintype "bidirectional"))
    )
    (net (code "44") (name "Net-(U3-RT_CLK)") (class "Default")
      (node (ref "R7") (pin "2") (pinfunction "2_2") (pintype "passive"))
      (node (ref "U3") (pin "1") (pinfunction "RT_CLK_1") (pintype "bidirectional"))
    )
    (net (code "45") (name "Net-(U3-SS)") (class "Default")
      (node (ref "C15") (pin "2") (pinfunction "2_2") (pintype "passive"))
      (node (ref "U3") (pin "2") (pinfunction "SS_2") (pintype "bidirectional"))
    )
    (net (code "46") (name "Net-(U3-SW)") (class "Default")
      (node (ref "C20") (pin "1") (pinfunction "1_1") (pintype "passive"))
      (node (ref "L3") (pin "2") (pinfunction "2_2") (pintype "passive"))
      (node (ref "Q1") (pin "P$5") (pinfunction "D_P$5") (pintype "passive"))
      (node (ref "Q1") (pin "P$6") (pinfunction "D_P$6") (pintype "passive"))
      (node (ref "Q1") (pin "P$7") (pinfunction "D_P$7") (pintype "passive"))
      (node (ref "Q1") (pin "P$8") (pinfunction "D_P$8") (pintype "passive"))
      (node (ref "Q1") (pin "P$9") (pinfunction "D_P$9") (pintype "passive"))
      (node (ref "Q2") (pin "P$1") (pinfunction "S_P$1") (pintype "passive"))
      (node (ref "Q2") (pin "P$2") (pinfunction "S_P$2") (pintype "passive"))
      (node (ref "Q2") (pin "P$3") (pinfunction "S_P$3") (pintype "passive"))
      (node (ref "U3") (pin "12") (pinfunction "SW_12") (pintype "bidirectional"))
    )
    (net (code "47") (name "Net-(U3-VCC)") (class "Default")
      (node (ref "R8") (pin "1") (pinfunction "1_1") (pintype "passive"))
      (node (ref "U3") (pin "10") (pinfunction "VCC_10") (pintype "bidirectional"))
    )
    (net (code "48") (name "Net-(U4-BOOT)") (class "Default")
      (node (ref "C29") (pin "1") (pinfunction "1_1") (pintype "passive"))
      (node (ref "U4") (pin "1") (pinfunction "BOOT_1") (pintype "bidirectional"))
    )
    (net (code "49") (name "Net-(U4-FB)") (class "Default")
      (node (ref "C30") (pin "1") (pinfunction "1_1") (pintype "passive"))
      (node (ref "R14") (pin "1") (pinfunction "1_1") (pintype "passive"))
      (node (ref "R15") (pin "2") (pinfunction "2_2") (pintype "passive"))
      (node (ref "U4") (pin "5") (pinfunction "FB_5") (pintype "bidirectional"))
    )
    (net (code "50") (name "Net-(U4-RT)") (class "Default")
      (node (ref "R13") (pin "2") (pinfunction "2_2") (pintype "passive"))
      (node (ref "U4") (pin "4") (pinfunction "RT_4") (pintype "bidirectional"))
    )
    (net (code "51") (name "Net-(U4-SS)") (class "Default")
      (node (ref "C28") (pin "1") (pinfunction "1_1") (pintype "passive"))
      (node (ref "U4") (pin "6") (pinfunction "SS_6") (pintype "bidirectional"))
    )
    (net (code "52") (name "Net-(U5-ADR0)") (class "Default")
      (node (ref "R21") (pin "1") (pinfunction "1_1") (pintype "passive"))
      (node (ref "U5") (pin "13") (pinfunction "ADR0_13") (pintype "bidirectional"))
    )
    (net (code "53") (name "Net-(U5-GPIO0)") (class "Default")
      (node (ref "R18") (pin "1") (pinfunction "1_1") (pintype "passive"))
      (node (ref "R19") (pin "2") (pinfunction "2_2") (pintype "passive"))
      (node (ref "U5") (pin "12") (pinfunction "GPIO0_12") (pintype "bidirectional"))
    )
    (net (code "54") (name "Net-(U5-GPIO1)") (class "Default")
      (node (ref "R17") (pin "1") (pinfunction "1_1") (pintype "passive"))
      (node (ref "R18") (pin "2") (pinfunction "2_2") (pintype "passive"))
      (node (ref "U5") (pin "11") (pinfunction "GPIO1_11") (pintype "bidirectional"))
    )
    (net (code "55") (name "Net-(U5-GPIO2)") (class "Default")
      (node (ref "R16") (pin "1") (pinfunction "1_1") (pintype "passive"))
      (node (ref "R17") (pin "2") (pinfunction "2_2") (pintype "passive"))
      (node (ref "U5") (pin "14") (pinfunction "GPIO2_14") (pintype "bidirectional"))
    )
    (net (code "56") (name "Net-(U5-GPIO3)") (class "Default")
      (node (ref "R15") (pin "1") (pinfunction "1_1") (pintype "passive"))
      (node (ref "R16") (pin "2") (pinfunction "2_2") (pintype "passive"))
      (node (ref "U5") (pin "15") (pinfunction "GPIO3_15") (pintype "bidirectional"))
    )
    (net (code "57") (name "Net-(U5-VBUS_EN_SRC)") (class "Default")
      (node (ref "R25") (pin "1") (pinfunction "1_1") (pintype "passive"))
      (node (ref "U5") (pin "20") (pinfunction "VBUS_EN_SRC_20") (pintype "bidirectional"))
    )
    (net (code "58") (name "Net-(U5-VREG_1V2)") (class "Default")
      (node (ref "C34") (pin "1") (pinfunction "1_1") (pintype "passive"))
      (node (ref "U5") (pin "21") (pinfunction "VREG_1V2_21") (pintype "bidirectional"))
    )
    (net (code "59") (name "Net-(U5-VREG_2V7)") (class "Default")
      (node (ref "C33") (pin "1") (pinfunction "1_1") (pintype "passive"))
      (node (ref "U5") (pin "23") (pinfunction "VREG_2V7_23") (pintype "bidirectional"))
    )
    (net (code "60") (name "Net-(U6-DISCH)") (class "Default")
      (node (ref "R30") (pin "2") (pinfunction "2_2") (pintype "passive"))
      (node (ref "U6") (pin "9") (pinfunction "DISCH_9") (pintype "bidirectional"))
    )
    (net (code "61") (name "Net-(U6-VBUS_DISCH)") (class "Default")
      (node (ref "R26") (pin "1") (pinfunction "1_1") (pintype "passive"))
      (node (ref "U6") (pin "18") (pinfunction "VBUS_DISCH_18") (pintype "bidirectional"))
    )
    (net (code "62") (name "Net-(U6-VBUS_EN_SNK)") (class "Default")
      (node (ref "R28") (pin "1") (pinfunction "1_1") (pintype "passive"))
      (node (ref "U6") (pin "16") (pinfunction "VBUS_EN_SNK_16") (pintype "bidirectional"))
    )
    (net (code "63") (name "Net-(U6-VCONN)") (class "Default")
      (node (ref "C36") (pin "2") (pinfunction "2_2") (pintype "passive"))
      (node (ref "C37") (pin "2") (pinfunction "2_2") (pintype "passive"))
      (node (ref "U6") (pin "22") (pinfunction "VSYS_22") (pintype "bidirectional"))
      (node (ref "U6") (pin "3") (pinfunction "VCONN_3") (pintype "bidirectional"))
    )
    (net (code "64") (name "Net-(U6-VREG_1V2)") (class "Default")
      (node (ref "C36") (pin "1") (pinfunction "1_1") (pintype "passive"))
      (node (ref "U6") (pin "21") (pinfunction "VREG_1V2_21") (pintype "bidirectional"))
    )
    (net (code "65") (name "PGND") (class "Default")
      (node (ref "C1") (pin "2") (pinfunction "-_2") (pintype "passive"))
      (node (ref "C10") (pin "2") (pinfunction "2_2") (pintype "passive"))
      (node (ref "C11") (pin "2") (pinfunction "2_2") (pintype "passive"))
      (node (ref "C12") (pin "2") (pinfunction "2_2") (pintype "passive"))
      (node (ref "C13") (pin "2") (pinfunction "2_2") (pintype "passive"))
      (node (ref "C14") (pin "2") (pinfunction "2_2") (pintype "passive"))
      (node (ref "C2") (pin "2") (pinfunction "2_2") (pintype "passive"))
      (node (ref "C21") (pin "2") (pinfunction "2_2") (pintype "passive"))
      (node (ref "C22") (pin "2") (pinfunction "2_2") (pintype "passive"))
      (node (ref "C23") (pin "2") (pinfunction "2_2") (pintype "passive"))
      (node (ref "C24") (pin "2") (pinfunction "2_2") (pintype "passive"))
      (node (ref "C25") (pin "2") (pinfunction "-_2") (pintype "passive"))
      (node (ref "C26") (pin "2") (pinfunction "2_2") (pintype "passive"))
      (node (ref "C27") (pin "2") (pinfunction "2_2") (pintype "passive"))
      (node (ref "C28") (pin "2") (pinfunction "2_2") (pintype "passive"))
      (node (ref "C3") (pin "1") (pinfunction "1_1") (pintype "passive"))
      (node (ref "C31") (pin "2") (pinfunction "-_2") (pintype "passive"))
      (node (ref "C33") (pin "2") (pinfunction "2_2") (pintype "passive"))
      (node (ref "C34") (pin "2") (pinfunction "2_2") (pintype "passive"))
      (node (ref "C35") (pin "2") (pinfunction "2_2") (pintype "passive"))
      (node (ref "C4") (pin "1") (pinfunction "1_1") (pintype "passive"))
      (node (ref "C5") (pin "2") (pinfunction "2_2") (pintype "passive"))
      (node (ref "C8") (pin "2") (pinfunction "-_2") (pintype "passive"))
      (node (ref "C9") (pin "2") (pinfunction "-_2") (pintype "passive"))
      (node (ref "D2") (pin "2") (pinfunction "A_2") (pintype "passive"))
      (node (ref "D4") (pin "2") (pinfunction "A_2") (pintype "passive"))
      (node (ref "J1") (pin "4") (pinfunction "GND_4") (pintype "bidirectional"))
      (node (ref "J1") (pin "SHELL") (pinfunction "SHIELD_SHELL") (pintype "bidirectional"))
      (node (ref "J1") (pin "SHELL1") (pinfunction "SHIELD_SHELL1") (pintype "bidirectional"))
      (node (ref "J1") (pin "SHELL2") (pinfunction "SHIELD_SHELL2") (pintype "bidirectional"))
      (node (ref "J2") (pin "4") (pinfunction "GND_4") (pintype "bidirectional"))
      (node (ref "J2") (pin "SHELL") (pinfunction "SHIELD_SHELL") (pintype "bidirectional"))
      (node (ref "J2") (pin "SHELL1") (pinfunction "SHIELD_SHELL1") (pintype "bidirectional"))
      (node (ref "J2") (pin "SHELL2") (pinfunction "SHIELD_SHELL2") (pintype "bidirectional"))
      (node (ref "J3") (pin "P$1") (pinfunction "A1/B12_P$1") (pintype "bidirectional"))
      (node (ref "J3") (pin "P$12") (pinfunction "A12/B1_P$12") (pintype "bidirectional"))
      (node (ref "J3") (pin "P$13") (pinfunction "A1/B12_P$13") (pintype "bidirectional"))
      (node (ref "J3") (pin "P$14") (pinfunction "A12/B1_P$14") (pintype "bidirectional"))
      (node (ref "J3") (pin "P$15") (pinfunction "A1/B12_P$15") (pintype "bidirectional"))
      (node (ref "J3") (pin "P$16") (pinfunction "A12/B1_P$16") (pintype "bidirectional"))
      (node (ref "J4") (pin "2") (pinfunction "2_2") (pintype "passive"))
      (node (ref "J4") (pin "S1") (pinfunction "SHIELD_S1") (pintype "passive"))
      (node (ref "J4") (pin "S2") (pinfunction "SHIELD_S2") (pintype "passive"))
      (node (ref "J4") (pin "S3") (pinfunction "SHIELD_S3") (pintype "passive"))
      (node (ref "J4") (pin "S4") (pinfunction "SHIELD_S4") (pintype "passive"))
      (node (ref "Q1") (pin "P$1") (pinfunction "S_P$1") (pintype "passive"))
      (node (ref "Q1") (pin "P$2") (pinfunction "S_P$2") (pintype "passive"))
      (node (ref "Q1") (pin "P$3") (pinfunction "S_P$3") (pintype "passive"))
      (node (ref "R13") (pin "1") (pinfunction "1_1") (pintype "passive"))
      (node (ref "R20") (pin "1") (pinfunction "1_1") (pintype "passive"))
      (node (ref "R21") (pin "2") (pinfunction "2_2") (pintype "passive"))
      (node (ref "R22") (pin "1") (pinfunction "1_1") (pintype "passive"))
      (node (ref "U$1") (pin "3") (pinfunction "A_3") (pintype "passive"))
      (node (ref "U1") (pin "9") (pinfunction "GND_9") (pintype "bidirectional"))
      (node (ref "U2") (pin "9") (pinfunction "GND_9") (pintype "bidirectional"))
      (node (ref "U3") (pin "17") (pinfunction "PWRPAD_17") (pintype "bidirectional"))
      (node (ref "U3") (pin "9") (pinfunction "PGND_9") (pintype "bidirectional"))
      (node (ref "U4") (pin "7") (pinfunction "GND_7") (pintype "bidirectional"))
      (node (ref "U4") (pin "9") (pinfunction "PAD_9") (pintype "bidirectional"))
      (node (ref "U5") (pin "1") (pinfunction "CC1GND_1") (pintype "bidirectional"))
      (node (ref "U5") (pin "10") (pinfunction "GND_10") (pintype "bidirectional"))
      (node (ref "U5") (pin "25") (pinfunction "PAD_25") (pintype "bidirectional"))
      (node (ref "U5") (pin "5") (pinfunction "CC2GND_5") (pintype "bidirectional"))
      (node (ref "U5") (pin "6") (pinfunction "RESET_6") (pintype "bidirectional"))
      (node (ref "U6") (pin "10") (pinfunction "GND_10") (pintype "bidirectional"))
      (node (ref "U6") (pin "12") (pinfunction "ADR0_12") (pintype "bidirectional"))
      (node (ref "U6") (pin "13") (pinfunction "ADR1_13") (pintype "bidirectional"))
      (node (ref "U6") (pin "25") (pinfunction "PAD_25") (pintype "bidirectional"))
      (node (ref "U6") (pin "6") (pinfunction "RESET_6") (pintype "bidirectional"))
    )
    (net (code "66") (name "QCDM1") (class "Default")
      (node (ref "J1") (pin "2") (pinfunction "D-_2") (pintype "bidirectional"))
      (node (ref "U1") (pin "5") (pinfunction "DM_5") (pintype "bidirectional"))
    )
    (net (code "67") (name "QCDM2") (class "Default")
      (node (ref "J2") (pin "2") (pinfunction "D-_2") (pintype "bidirectional"))
      (node (ref "U2") (pin "5") (pinfunction "DM_5") (pintype "bidirectional"))
    )
    (net (code "68") (name "QCDP1") (class "Default")
      (node (ref "J1") (pin "3") (pinfunction "D+_3") (pintype "bidirectional"))
      (node (ref "U1") (pin "6") (pinfunction "DP_6") (pintype "bidirectional"))
    )
    (net (code "69") (name "QCDP2") (class "Default")
      (node (ref "J2") (pin "3") (pinfunction "D+_3") (pintype "bidirectional"))
      (node (ref "U2") (pin "6") (pinfunction "DP_6") (pintype "bidirectional"))
    )
    (net (code "70") (name "SCL") (class "Default")
      (node (ref "U5") (pin "7") (pinfunction "SCL_7") (pintype "bidirectional"))
    )
    (net (code "71") (name "SDA") (class "Default")
      (node (ref "U5") (pin "8") (pinfunction "SDA_8") (pintype "bidirectional"))
    )
    (net (code "72") (name "VBUS") (class "Default")
      (node (ref "C12") (pin "1") (pinfunction "1_1") (pintype "passive"))
      (node (ref "C13") (pin "1") (pinfunction "1_1") (pintype "passive"))
      (node (ref "C14") (pin "1") (pinfunction "1_1") (pintype "passive"))
      (node (ref "C19") (pin "1") (pinfunction "1_1") (pintype "passive"))
      (node (ref "R3") (pin "2") (pinfunction "2_2") (pintype "passive"))
      (node (ref "R4") (pin "1") (pinfunction "1_1") (pintype "passive"))
      (node (ref "U3") (pin "7") (pinfunction "VIN_7") (pintype "bidirectional"))
    )
    (net (code "73") (name "unconnected-(J3-A6-PadP$6)") (class "Default")
      (node (ref "J3") (pin "P$6") (pinfunction "A6_P$6") (pintype "bidirectional"))
    )
    (net (code "74") (name "unconnected-(J3-A7-PadP$8)") (class "Default")
      (node (ref "J3") (pin "P$8") (pinfunction "A7_P$8") (pintype "bidirectional"))
    )
    (net (code "75") (name "unconnected-(J3-A8-PadP$10)") (class "Default")
      (node (ref "J3") (pin "P$10") (pinfunction "A8_P$10") (pintype "bidirectional"))
    )
    (net (code "76") (name "unconnected-(J3-B6-PadP$7)") (class "Default")
      (node (ref "J3") (pin "P$7") (pinfunction "B6_P$7") (pintype "bidirectional"))
    )
    (net (code "77") (name "unconnected-(J3-B7-PadP$5)") (class "Default")
      (node (ref "J3") (pin "P$5") (pinfunction "B7_P$5") (pintype "bidirectional"))
    )
    (net (code "78") (name "unconnected-(J3-B8-PadP$3)") (class "Default")
      (node (ref "J3") (pin "P$3") (pinfunction "B8_P$3") (pintype "bidirectional"))
    )
    (net (code "79") (name "unconnected-(J5-A6-PadP$6)") (class "Default")
      (node (ref "J5") (pin "P$6") (pinfunction "A6_P$6") (pintype "bidirectional"))
    )
    (net (code "80") (name "unconnected-(J5-A7-PadP$8)") (class "Default")
      (node (ref "J5") (pin "P$8") (pinfunction "A7_P$8") (pintype "bidirectional"))
    )
    (net (code "81") (name "unconnected-(J5-A8-PadP$10)") (class "Default")
      (node (ref "J5") (pin "P$10") (pinfunction "A8_P$10") (pintype "bidirectional"))
    )
    (net (code "82") (name "unconnected-(J5-B6-PadP$7)") (class "Default")
      (node (ref "J5") (pin "P$7") (pinfunction "B6_P$7") (pintype "bidirectional"))
    )
    (net (code "83") (name "unconnected-(J5-B7-PadP$5)") (class "Default")
      (node (ref "J5") (pin "P$5") (pinfunction "B7_P$5") (pintype "bidirectional"))
    )
    (net (code "84") (name "unconnected-(J5-B8-PadP$3)") (class "Default")
      (node (ref "J5") (pin "P$3") (pinfunction "B8_P$3") (pintype "bidirectional"))
    )
    (net (code "85") (name "unconnected-(U1-NC-Pad4)") (class "Default")
      (node (ref "U1") (pin "4") (pinfunction "NC_4") (pintype "bidirectional"))
    )
    (net (code "86") (name "unconnected-(U2-NC-Pad4)") (class "Default")
      (node (ref "U2") (pin "4") (pinfunction "NC_4") (pintype "bidirectional"))
    )
    (net (code "87") (name "unconnected-(U5-A_B_SIDE-Pad17)") (class "Default")
      (node (ref "U5") (pin "17") (pinfunction "A_B_SIDE_17") (pintype "bidirectional"))
    )
    (net (code "88") (name "unconnected-(U5-GPIO4-Pad16)") (class "Default")
      (node (ref "U5") (pin "16") (pinfunction "GPIO4_16") (pintype "bidirectional"))
    )
    (net (code "89") (name "unconnected-(U5-VCONN-Pad3)") (class "Default")
      (node (ref "U5") (pin "3") (pinfunction "VCONN_3") (pintype "bidirectional"))
    )
    (net (code "90") (name "unconnected-(U5-VSYS-Pad22)") (class "Default")
      (node (ref "U5") (pin "22") (pinfunction "VSYS_22") (pintype "bidirectional"))
    )
    (net (code "91") (name "unconnected-(U6-ALERT-Pad19)") (class "Default")
      (node (ref "U6") (pin "19") (pinfunction "ALERT_19") (pintype "bidirectional"))
    )
    (net (code "92") (name "unconnected-(U6-ATTACH-Pad11)") (class "Default")
      (node (ref "U6") (pin "11") (pinfunction "ATTACH_11") (pintype "bidirectional"))
    )
    (net (code "93") (name "unconnected-(U6-A_B_SIDE-Pad17)") (class "Default")
      (node (ref "U6") (pin "17") (pinfunction "A_B_SIDE_17") (pintype "bidirectional"))
    )
    (net (code "94") (name "unconnected-(U6-GPIO-Pad15)") (class "Default")
      (node (ref "U6") (pin "15") (pinfunction "GPIO_15") (pintype "bidirectional"))
    )
    (net (code "95") (name "unconnected-(U6-POWER_OK2-Pad20)") (class "Default")
      (node (ref "U6") (pin "20") (pinfunction "POWER_OK2_20") (pintype "bidirectional"))
    )
    (net (code "96") (name "unconnected-(U6-POWER_OK3-Pad14)") (class "Default")
      (node (ref "U6") (pin "14") (pinfunction "POWER_OK3_14") (pintype "bidirectional"))
    )
    (net (code "97") (name "unconnected-(U6-SCL-Pad7)") (class "Default")
      (node (ref "U6") (pin "7") (pinfunction "SCL_7") (pintype "bidirectional"))
    )
    (net (code "98") (name "unconnected-(U6-SDA-Pad8)") (class "Default")
      (node (ref "U6") (pin "8") (pinfunction "SDA_8") (pintype "bidirectional"))
    )
  )
)
